# rgb_led_watch_2.net
KiCad netlist of a schematic drawn in EAGLE
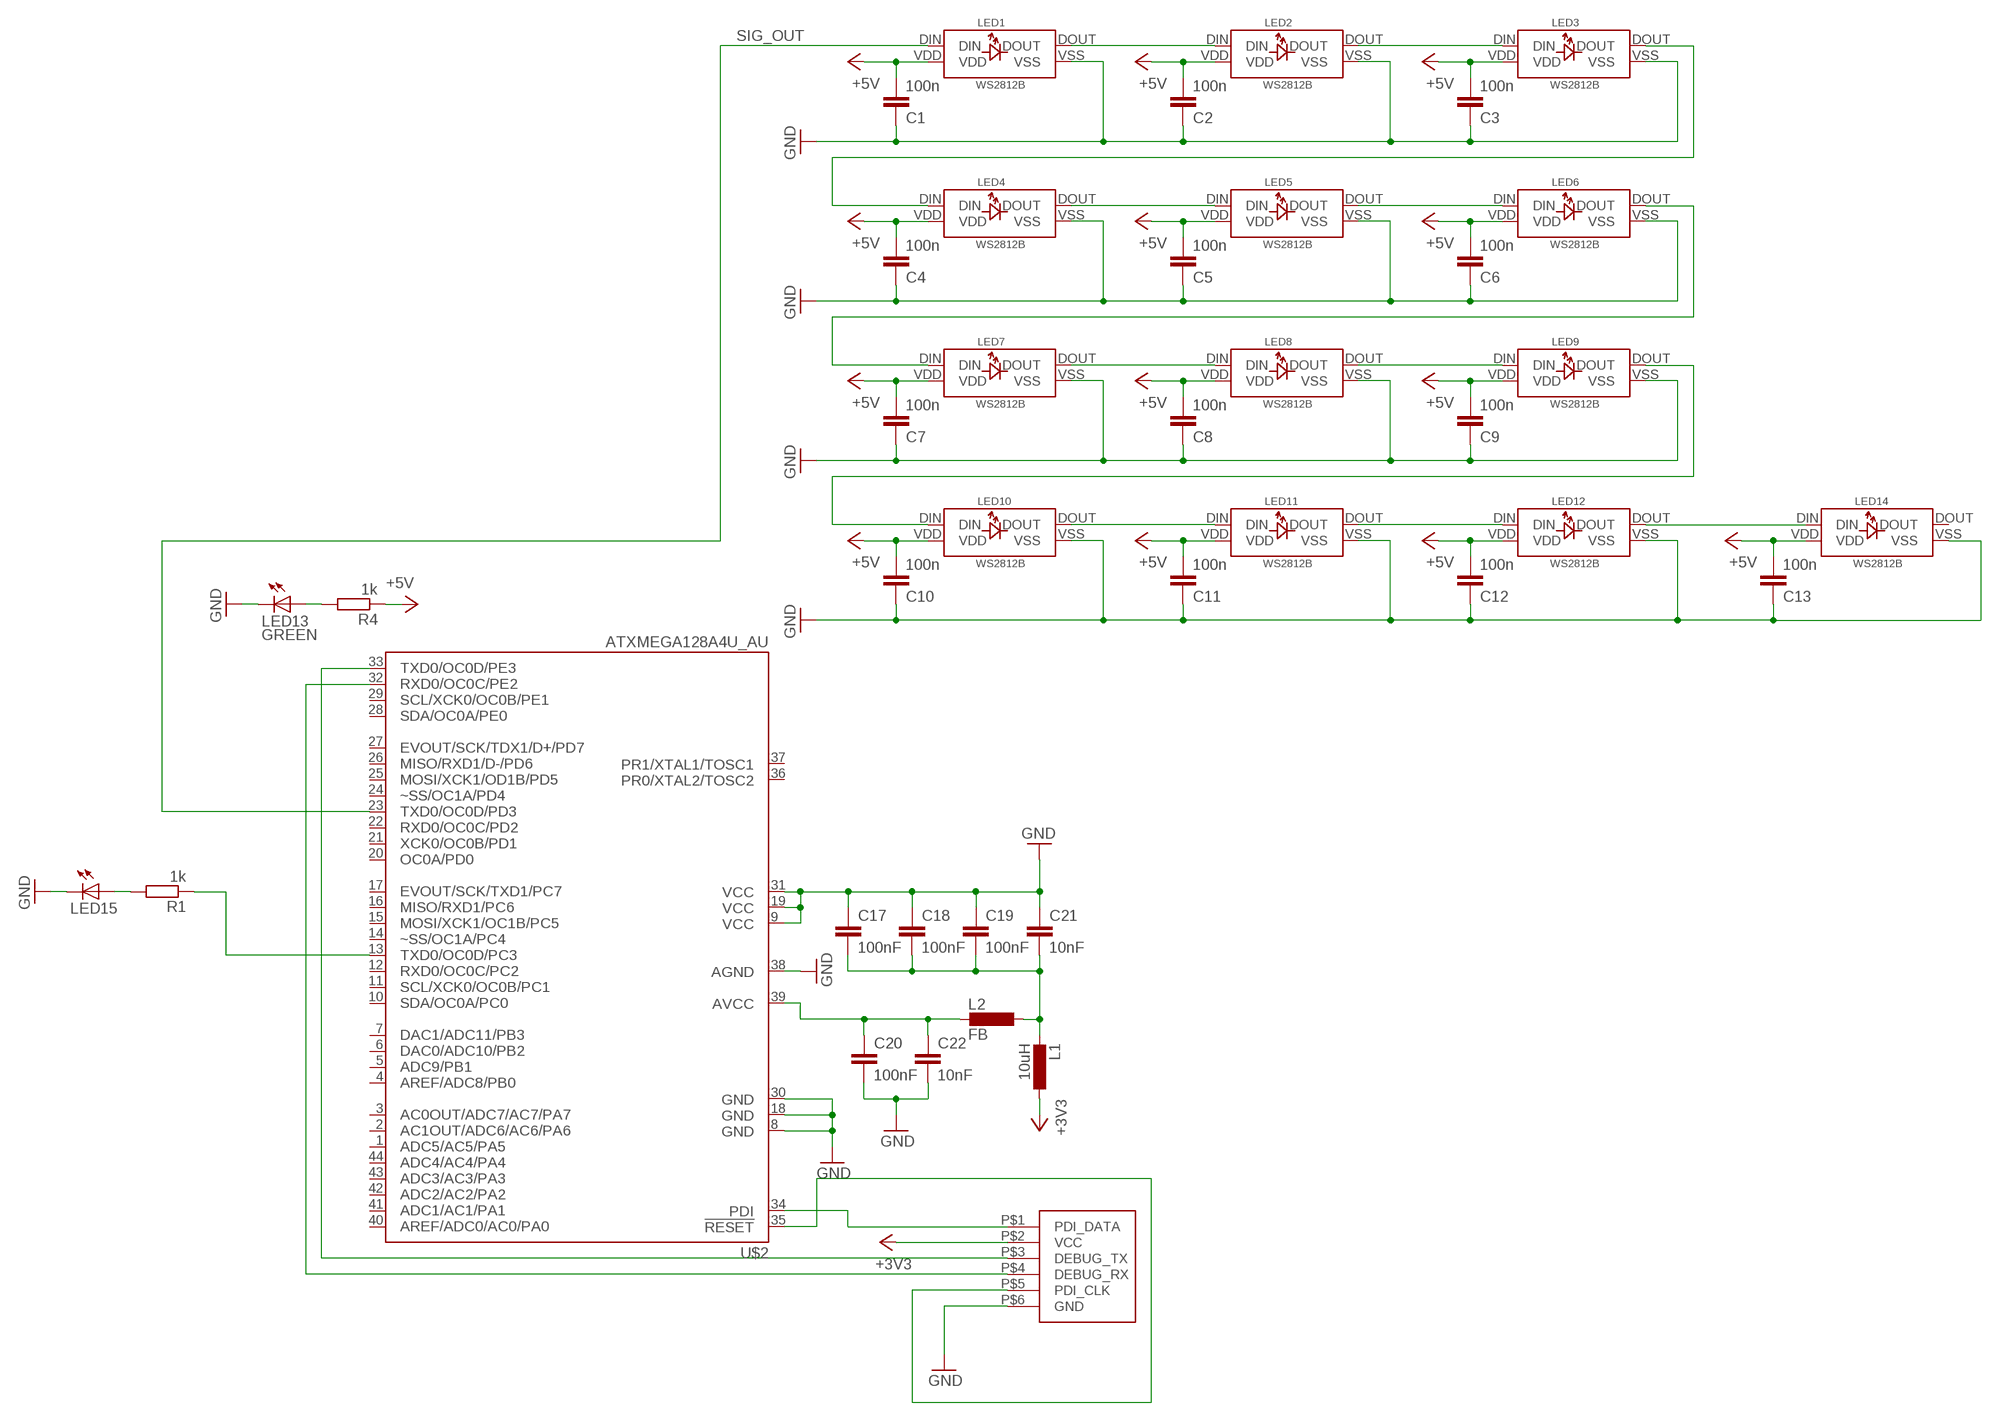
[diagram p0: schematic, sheet 1]

(export (version "E")
  (design (tool "Eeschema 10.0.6"))
  (components
    (comp (ref "C1")
      (value "100n")
      (footprint "eagle-import:C0603")
      (libsource (lib "eagle-import") (part "resistor_C-EUC0603"))
    )
    (comp (ref "C2")
      (value "100n")
      (footprint "eagle-import:C0603")
      (libsource (lib "eagle-import") (part "resistor_C-EUC0603"))
    )
    (comp (ref "C3")
      (value "100n")
      (footprint "eagle-import:C0603")
      (libsource (lib "eagle-import") (part "resistor_C-EUC0603"))
    )
    (comp (ref "C4")
      (value "100n")
      (footprint "eagle-import:C0603")
      (libsource (lib "eagle-import") (part "resistor_C-EUC0603"))
    )
    (comp (ref "C5")
      (value "100n")
      (footprint "eagle-import:C0603")
      (libsource (lib "eagle-import") (part "resistor_C-EUC0603"))
    )
    (comp (ref "C6")
      (value "100n")
      (footprint "eagle-import:C0603")
      (libsource (lib "eagle-import") (part "resistor_C-EUC0603"))
    )
    (comp (ref "C7")
      (value "100n")
      (footprint "eagle-import:C0603")
      (libsource (lib "eagle-import") (part "resistor_C-EUC0603"))
    )
    (comp (ref "C8")
      (value "100n")
      (footprint "eagle-import:C0603")
      (libsource (lib "eagle-import") (part "resistor_C-EUC0603"))
    )
    (comp (ref "C9")
      (value "100n")
      (footprint "eagle-import:C0603")
      (libsource (lib "eagle-import") (part "resistor_C-EUC0603"))
    )
    (comp (ref "C10")
      (value "100n")
      (footprint "eagle-import:C0603")
      (libsource (lib "eagle-import") (part "resistor_C-EUC0603"))
    )
    (comp (ref "C11")
      (value "100n")
      (footprint "eagle-import:C0603")
      (libsource (lib "eagle-import") (part "resistor_C-EUC0603"))
    )
    (comp (ref "C12")
      (value "100n")
      (footprint "eagle-import:C0603")
      (libsource (lib "eagle-import") (part "resistor_C-EUC0603"))
    )
    (comp (ref "C13")
      (value "100n")
      (footprint "eagle-import:C0603")
      (libsource (lib "eagle-import") (part "resistor_C-EUC0603"))
    )
    (comp (ref "C17")
      (value "100nF")
      (footprint "eagle-import:C0306")
      (libsource (lib "eagle-import") (part "C-EUC0306"))
    )
    (comp (ref "C18")
      (value "100nF")
      (footprint "eagle-import:C0306")
      (libsource (lib "eagle-import") (part "C-EUC0306"))
    )
    (comp (ref "C19")
      (value "100nF")
      (footprint "eagle-import:C0306")
      (libsource (lib "eagle-import") (part "C-EUC0306"))
    )
    (comp (ref "C20")
      (value "100nF")
      (footprint "eagle-import:C0306")
      (libsource (lib "eagle-import") (part "C-EUC0306"))
    )
    (comp (ref "C21")
      (value "10nF")
      (footprint "eagle-import:C0805")
      (libsource (lib "eagle-import") (part "C-EUC0805"))
    )
    (comp (ref "C22")
      (value "10nF")
      (footprint "eagle-import:C0805")
      (libsource (lib "eagle-import") (part "C-EUC0805"))
    )
    (comp (ref "L1")
      (value "10uH")
      (footprint "eagle-import:R0805")
      (libsource (lib "eagle-import") (part "L-EUSMD0805"))
    )
    (comp (ref "L2")
      (value "FB")
      (footprint "eagle-import:R0603")
      (libsource (lib "eagle-import") (part "L-EUSMD0603"))
    )
    (comp (ref "LED1")
      (value "WS2812B")
      (footprint "eagle-import:WS2812B")
      (libsource (lib "eagle-import") (part "WS2812B"))
    )
    (comp (ref "LED2")
      (value "WS2812B")
      (footprint "eagle-import:WS2812B")
      (libsource (lib "eagle-import") (part "WS2812B"))
    )
    (comp (ref "LED3")
      (value "WS2812B")
      (footprint "eagle-import:WS2812B")
      (libsource (lib "eagle-import") (part "WS2812B"))
    )
    (comp (ref "LED4")
      (value "WS2812B")
      (footprint "eagle-import:WS2812B")
      (libsource (lib "eagle-import") (part "WS2812B"))
    )
    (comp (ref "LED5")
      (value "WS2812B")
      (footprint "eagle-import:WS2812B")
      (libsource (lib "eagle-import") (part "WS2812B"))
    )
    (comp (ref "LED6")
      (value "WS2812B")
      (footprint "eagle-import:WS2812B")
      (libsource (lib "eagle-import") (part "WS2812B"))
    )
    (comp (ref "LED7")
      (value "WS2812B")
      (footprint "eagle-import:WS2812B")
      (libsource (lib "eagle-import") (part "WS2812B"))
    )
    (comp (ref "LED8")
      (value "WS2812B")
      (footprint "eagle-import:WS2812B")
      (libsource (lib "eagle-import") (part "WS2812B"))
    )
    (comp (ref "LED9")
      (value "WS2812B")
      (footprint "eagle-import:WS2812B")
      (libsource (lib "eagle-import") (part "WS2812B"))
    )
    (comp (ref "LED10")
      (value "WS2812B")
      (footprint "eagle-import:WS2812B")
      (libsource (lib "eagle-import") (part "WS2812B"))
    )
    (comp (ref "LED11")
      (value "WS2812B")
      (footprint "eagle-import:WS2812B")
      (libsource (lib "eagle-import") (part "WS2812B"))
    )
    (comp (ref "LED12")
      (value "WS2812B")
      (footprint "eagle-import:WS2812B")
      (libsource (lib "eagle-import") (part "WS2812B"))
    )
    (comp (ref "LED13")
      (value "GREEN")
      (footprint "eagle-import:CHIPLED_0603")
      (libsource (lib "eagle-import") (part "LEDCHIPLED_0603"))
    )
    (comp (ref "LED14")
      (value "WS2812B")
      (footprint "eagle-import:WS2812B")
      (libsource (lib "eagle-import") (part "WS2812B"))
    )
    (comp (ref "LED15")
      (value "LED5MM")
      (footprint "eagle-import:LED5MM")
      (libsource (lib "eagle-import") (part "LED5MM"))
    )
    (comp (ref "R1")
      (value "1k")
      (footprint "eagle-import:R0603")
      (libsource (lib "eagle-import") (part "R-EU_R0603"))
    )
    (comp (ref "R4")
      (value "1k")
      (footprint "eagle-import:R0603")
      (libsource (lib "eagle-import") (part "R-EU_R0603"))
    )
    (comp (ref "U$1")
      (value "CON_PROG-6CORN")
      (footprint "eagle-import:SMD-6-CORNER")
      (libsource (lib "eagle-import") (part "CON_PROG-6CORN"))
    )
    (comp (ref "U$2")
      (value "ATXMEGA128A4U_AU")
      (footprint "eagle-import:TQFP44")
      (libsource (lib "eagle-import") (part "ATXMEGAA4U_AU128"))
    )
  )
  (nets
    (net (code "1") (name "+3V3") (class "Default")
      (node (ref "L1") (pin "1") (pinfunction "1_1") (pintype "passive"))
      (node (ref "U$1") (pin "P$2") (pinfunction "VCC_P$2") (pintype "bidirectional"))
    )
    (net (code "2") (name "+5V") (class "Default")
      (node (ref "C1") (pin "2") (pinfunction "2_2") (pintype "passive"))
      (node (ref "C10") (pin "2") (pinfunction "2_2") (pintype "passive"))
      (node (ref "C11") (pin "2") (pinfunction "2_2") (pintype "passive"))
      (node (ref "C12") (pin "2") (pinfunction "2_2") (pintype "passive"))
      (node (ref "C13") (pin "2") (pinfunction "2_2") (pintype "passive"))
      (node (ref "C2") (pin "2") (pinfunction "2_2") (pintype "passive"))
      (node (ref "C3") (pin "2") (pinfunction "2_2") (pintype "passive"))
      (node (ref "C4") (pin "2") (pinfunction "2_2") (pintype "passive"))
      (node (ref "C5") (pin "2") (pinfunction "2_2") (pintype "passive"))
      (node (ref "C6") (pin "2") (pinfunction "2_2") (pintype "passive"))
      (node (ref "C7") (pin "2") (pinfunction "2_2") (pintype "passive"))
      (node (ref "C8") (pin "2") (pinfunction "2_2") (pintype "passive"))
      (node (ref "C9") (pin "2") (pinfunction "2_2") (pintype "passive"))
      (node (ref "LED1") (pin "VDD") (pinfunction "VDD_VDD") (pintype "power_in"))
      (node (ref "LED10") (pin "VDD") (pinfunction "VDD_VDD") (pintype "power_in"))
      (node (ref "LED11") (pin "VDD") (pinfunction "VDD_VDD") (pintype "power_in"))
      (node (ref "LED12") (pin "VDD") (pinfunction "VDD_VDD") (pintype "power_in"))
      (node (ref "LED14") (pin "VDD") (pinfunction "VDD_VDD") (pintype "power_in"))
      (node (ref "LED2") (pin "VDD") (pinfunction "VDD_VDD") (pintype "power_in"))
      (node (ref "LED3") (pin "VDD") (pinfunction "VDD_VDD") (pintype "power_in"))
      (node (ref "LED4") (pin "VDD") (pinfunction "VDD_VDD") (pintype "power_in"))
      (node (ref "LED5") (pin "VDD") (pinfunction "VDD_VDD") (pintype "power_in"))
      (node (ref "LED6") (pin "VDD") (pinfunction "VDD_VDD") (pintype "power_in"))
      (node (ref "LED7") (pin "VDD") (pinfunction "VDD_VDD") (pintype "power_in"))
      (node (ref "LED8") (pin "VDD") (pinfunction "VDD_VDD") (pintype "power_in"))
      (node (ref "LED9") (pin "VDD") (pinfunction "VDD_VDD") (pintype "power_in"))
      (node (ref "R4") (pin "1") (pinfunction "1_1") (pintype "passive"))
    )
    (net (code "3") (name "/SIG_OUT") (class "Default")
      (node (ref "LED1") (pin "DIN") (pinfunction "DIN_DIN") (pintype "input"))
      (node (ref "U$2") (pin "23") (pinfunction "PD3_23") (pintype "bidirectional"))
    )
    (net (code "4") (name "GND") (class "Default")
      (node (ref "C1") (pin "1") (pinfunction "1_1") (pintype "passive"))
      (node (ref "C10") (pin "1") (pinfunction "1_1") (pintype "passive"))
      (node (ref "C11") (pin "1") (pinfunction "1_1") (pintype "passive"))
      (node (ref "C12") (pin "1") (pinfunction "1_1") (pintype "passive"))
      (node (ref "C13") (pin "1") (pinfunction "1_1") (pintype "passive"))
      (node (ref "C17") (pin "1") (pinfunction "1_1") (pintype "passive"))
      (node (ref "C18") (pin "1") (pinfunction "1_1") (pintype "passive"))
      (node (ref "C19") (pin "1") (pinfunction "1_1") (pintype "passive"))
      (node (ref "C2") (pin "1") (pinfunction "1_1") (pintype "passive"))
      (node (ref "C20") (pin "2") (pinfunction "2_2") (pintype "passive"))
      (node (ref "C21") (pin "1") (pinfunction "1_1") (pintype "passive"))
      (node (ref "C22") (pin "2") (pinfunction "2_2") (pintype "passive"))
      (node (ref "C3") (pin "1") (pinfunction "1_1") (pintype "passive"))
      (node (ref "C4") (pin "1") (pinfunction "1_1") (pintype "passive"))
      (node (ref "C5") (pin "1") (pinfunction "1_1") (pintype "passive"))
      (node (ref "C6") (pin "1") (pinfunction "1_1") (pintype "passive"))
      (node (ref "C7") (pin "1") (pinfunction "1_1") (pintype "passive"))
      (node (ref "C8") (pin "1") (pinfunction "1_1") (pintype "passive"))
      (node (ref "C9") (pin "1") (pinfunction "1_1") (pintype "passive"))
      (node (ref "LED1") (pin "VSS") (pinfunction "VSS_VSS") (pintype "power_in"))
      (node (ref "LED10") (pin "VSS") (pinfunction "VSS_VSS") (pintype "power_in"))
      (node (ref "LED11") (pin "VSS") (pinfunction "VSS_VSS") (pintype "power_in"))
      (node (ref "LED12") (pin "VSS") (pinfunction "VSS_VSS") (pintype "power_in"))
      (node (ref "LED13") (pin "C") (pinfunction "C_C") (pintype "passive"))
      (node (ref "LED14") (pin "VSS") (pinfunction "VSS_VSS") (pintype "power_in"))
      (node (ref "LED15") (pin "K") (pinfunction "C_K") (pintype "passive"))
      (node (ref "LED2") (pin "VSS") (pinfunction "VSS_VSS") (pintype "power_in"))
      (node (ref "LED3") (pin "VSS") (pinfunction "VSS_VSS") (pintype "power_in"))
      (node (ref "LED4") (pin "VSS") (pinfunction "VSS_VSS") (pintype "power_in"))
      (node (ref "LED5") (pin "VSS") (pinfunction "VSS_VSS") (pintype "power_in"))
      (node (ref "LED6") (pin "VSS") (pinfunction "VSS_VSS") (pintype "power_in"))
      (node (ref "LED7") (pin "VSS") (pinfunction "VSS_VSS") (pintype "power_in"))
      (node (ref "LED8") (pin "VSS") (pinfunction "VSS_VSS") (pintype "power_in"))
      (node (ref "LED9") (pin "VSS") (pinfunction "VSS_VSS") (pintype "power_in"))
      (node (ref "U$1") (pin "P$6") (pinfunction "GND_P$6") (pintype "bidirectional"))
      (node (ref "U$2") (pin "18") (pinfunction "GND2_18") (pintype "bidirectional"))
      (node (ref "U$2") (pin "19") (pinfunction "VCC2_19") (pintype "bidirectional"))
      (node (ref "U$2") (pin "30") (pinfunction "GND3_30") (pintype "bidirectional"))
      (node (ref "U$2") (pin "31") (pinfunction "VCC3_31") (pintype "bidirectional"))
      (node (ref "U$2") (pin "38") (pinfunction "AGND_38") (pintype "bidirectional"))
      (node (ref "U$2") (pin "8") (pinfunction "GND1_8") (pintype "bidirectional"))
      (node (ref "U$2") (pin "9") (pinfunction "VCC1_9") (pintype "bidirectional"))
    )
    (net (code "5") (name "Net-(C17-Pad2)") (class "Default")
      (node (ref "C17") (pin "2") (pinfunction "2_2") (pintype "passive"))
      (node (ref "C18") (pin "2") (pinfunction "2_2") (pintype "passive"))
      (node (ref "C19") (pin "2") (pinfunction "2_2") (pintype "passive"))
      (node (ref "C21") (pin "2") (pinfunction "2_2") (pintype "passive"))
      (node (ref "L1") (pin "2") (pinfunction "2_2") (pintype "passive"))
      (node (ref "L2") (pin "1") (pinfunction "1_1") (pintype "passive"))
    )
    (net (code "6") (name "Net-(LED1-PadDOUT)") (class "Default")
      (node (ref "LED1") (pin "DOUT") (pinfunction "DOUT_DOUT") (pintype "output"))
      (node (ref "LED2") (pin "DIN") (pinfunction "DIN_DIN") (pintype "input"))
    )
    (net (code "7") (name "Net-(LED2-PadDOUT)") (class "Default")
      (node (ref "LED2") (pin "DOUT") (pinfunction "DOUT_DOUT") (pintype "output"))
      (node (ref "LED3") (pin "DIN") (pinfunction "DIN_DIN") (pintype "input"))
    )
    (net (code "8") (name "Net-(LED3-PadDOUT)") (class "Default")
      (node (ref "LED3") (pin "DOUT") (pinfunction "DOUT_DOUT") (pintype "output"))
      (node (ref "LED4") (pin "DIN") (pinfunction "DIN_DIN") (pintype "input"))
    )
    (net (code "9") (name "Net-(LED4-PadDOUT)") (class "Default")
      (node (ref "LED4") (pin "DOUT") (pinfunction "DOUT_DOUT") (pintype "output"))
      (node (ref "LED5") (pin "DIN") (pinfunction "DIN_DIN") (pintype "input"))
    )
    (net (code "10") (name "Net-(LED5-PadDOUT)") (class "Default")
      (node (ref "LED5") (pin "DOUT") (pinfunction "DOUT_DOUT") (pintype "output"))
      (node (ref "LED6") (pin "DIN") (pinfunction "DIN_DIN") (pintype "input"))
    )
    (net (code "11") (name "Net-(LED6-PadDOUT)") (class "Default")
      (node (ref "LED6") (pin "DOUT") (pinfunction "DOUT_DOUT") (pintype "output"))
      (node (ref "LED7") (pin "DIN") (pinfunction "DIN_DIN") (pintype "input"))
    )
    (net (code "12") (name "Net-(LED7-PadDOUT)") (class "Default")
      (node (ref "LED7") (pin "DOUT") (pinfunction "DOUT_DOUT") (pintype "output"))
      (node (ref "LED8") (pin "DIN") (pinfunction "DIN_DIN") (pintype "input"))
    )
    (net (code "13") (name "Net-(LED8-PadDOUT)") (class "Default")
      (node (ref "LED8") (pin "DOUT") (pinfunction "DOUT_DOUT") (pintype "output"))
      (node (ref "LED9") (pin "DIN") (pinfunction "DIN_DIN") (pintype "input"))
    )
    (net (code "14") (name "Net-(LED10-PadDIN)") (class "Default")
      (node (ref "LED10") (pin "DIN") (pinfunction "DIN_DIN") (pintype "input"))
      (node (ref "LED9") (pin "DOUT") (pinfunction "DOUT_DOUT") (pintype "output"))
    )
    (net (code "15") (name "Net-(LED10-PadDOUT)") (class "Default")
      (node (ref "LED10") (pin "DOUT") (pinfunction "DOUT_DOUT") (pintype "output"))
      (node (ref "LED11") (pin "DIN") (pinfunction "DIN_DIN") (pintype "input"))
    )
    (net (code "16") (name "Net-(LED11-PadDOUT)") (class "Default")
      (node (ref "LED11") (pin "DOUT") (pinfunction "DOUT_DOUT") (pintype "output"))
      (node (ref "LED12") (pin "DIN") (pinfunction "DIN_DIN") (pintype "input"))
    )
    (net (code "17") (name "Net-(LED12-PadDOUT)") (class "Default")
      (node (ref "LED12") (pin "DOUT") (pinfunction "DOUT_DOUT") (pintype "output"))
      (node (ref "LED14") (pin "DIN") (pinfunction "DIN_DIN") (pintype "input"))
    )
    (net (code "18") (name "Net-(LED13-PadA)") (class "Default")
      (node (ref "LED13") (pin "A") (pinfunction "A_A") (pintype "passive"))
      (node (ref "R4") (pin "2") (pinfunction "2_2") (pintype "passive"))
    )
    (net (code "19") (name "Net-(LED15-PadA)") (class "Default")
      (node (ref "LED15") (pin "A") (pinfunction "A_A") (pintype "passive"))
      (node (ref "R1") (pin "2") (pinfunction "2_2") (pintype "passive"))
    )
    (net (code "20") (name "Net-(U$1-DEBUG_RX)") (class "Default")
      (node (ref "U$1") (pin "P$4") (pinfunction "DEBUG_RX_P$4") (pintype "bidirectional"))
      (node (ref "U$2") (pin "32") (pinfunction "PE2_32") (pintype "bidirectional"))
    )
    (net (code "21") (name "Net-(U$1-DEBUG_TX)") (class "Default")
      (node (ref "U$1") (pin "P$3") (pinfunction "DEBUG_TX_P$3") (pintype "bidirectional"))
      (node (ref "U$2") (pin "33") (pinfunction "PE3_33") (pintype "bidirectional"))
    )
    (net (code "22") (name "Net-(U$1-PDI_CLK)") (class "Default")
      (node (ref "U$1") (pin "P$5") (pinfunction "PDI_CLK_P$5") (pintype "bidirectional"))
      (node (ref "U$2") (pin "35") (pinfunction "RESET_35") (pintype "bidirectional"))
    )
    (net (code "23") (name "Net-(U$1-PDI_DATA)") (class "Default")
      (node (ref "U$1") (pin "P$1") (pinfunction "PDI_DATA_P$1") (pintype "bidirectional"))
      (node (ref "U$2") (pin "34") (pinfunction "PDI_DATA_34") (pintype "bidirectional"))
    )
    (net (code "24") (name "Net-(U$2-AVCC)") (class "Default")
      (node (ref "C20") (pin "1") (pinfunction "1_1") (pintype "passive"))
      (node (ref "C22") (pin "1") (pinfunction "1_1") (pintype "passive"))
      (node (ref "L2") (pin "2") (pinfunction "2_2") (pintype "passive"))
      (node (ref "U$2") (pin "39") (pinfunction "AVCC_39") (pintype "bidirectional"))
    )
    (net (code "25") (name "Net-(U$2-PC3)") (class "Default")
      (node (ref "R1") (pin "1") (pinfunction "1_1") (pintype "passive"))
      (node (ref "U$2") (pin "13") (pinfunction "PC3_13") (pintype "bidirectional"))
    )
    (net (code "26") (name "unconnected-(LED14-PadDOUT)") (class "Default")
      (node (ref "LED14") (pin "DOUT") (pinfunction "DOUT_DOUT") (pintype "output"))
    )
    (net (code "27") (name "unconnected-(U$2-PA0-Pad40)") (class "Default")
      (node (ref "U$2") (pin "40") (pinfunction "PA0_40") (pintype "bidirectional"))
    )
    (net (code "28") (name "unconnected-(U$2-PA1-Pad41)") (class "Default")
      (node (ref "U$2") (pin "41") (pinfunction "PA1_41") (pintype "bidirectional"))
    )
    (net (code "29") (name "unconnected-(U$2-PA2-Pad42)") (class "Default")
      (node (ref "U$2") (pin "42") (pinfunction "PA2_42") (pintype "bidirectional"))
    )
    (net (code "30") (name "unconnected-(U$2-PA3-Pad43)") (class "Default")
      (node (ref "U$2") (pin "43") (pinfunction "PA3_43") (pintype "bidirectional"))
    )
    (net (code "31") (name "unconnected-(U$2-PA4-Pad44)") (class "Default")
      (node (ref "U$2") (pin "44") (pinfunction "PA4_44") (pintype "bidirectional"))
    )
    (net (code "32") (name "unconnected-(U$2-PA5-Pad1)") (class "Default")
      (node (ref "U$2") (pin "1") (pinfunction "PA5_1") (pintype "bidirectional"))
    )
    (net (code "33") (name "unconnected-(U$2-PA6-Pad2)") (class "Default")
      (node (ref "U$2") (pin "2") (pinfunction "PA6_2") (pintype "bidirectional"))
    )
    (net (code "34") (name "unconnected-(U$2-PA7-Pad3)") (class "Default")
      (node (ref "U$2") (pin "3") (pinfunction "PA7_3") (pintype "bidirectional"))
    )
    (net (code "35") (name "unconnected-(U$2-PB0-Pad4)") (class "Default")
      (node (ref "U$2") (pin "4") (pinfunction "PB0_4") (pintype "bidirectional"))
    )
    (net (code "36") (name "unconnected-(U$2-PB1-Pad5)") (class "Default")
      (node (ref "U$2") (pin "5") (pinfunction "PB1_5") (pintype "bidirectional"))
    )
    (net (code "37") (name "unconnected-(U$2-PB2-Pad6)") (class "Default")
      (node (ref "U$2") (pin "6") (pinfunction "PB2_6") (pintype "bidirectional"))
    )
    (net (code "38") (name "unconnected-(U$2-PB3-Pad7)") (class "Default")
      (node (ref "U$2") (pin "7") (pinfunction "PB3_7") (pintype "bidirectional"))
    )
    (net (code "39") (name "unconnected-(U$2-PC0-Pad10)") (class "Default")
      (node (ref "U$2") (pin "10") (pinfunction "PC0_10") (pintype "bidirectional"))
    )
    (net (code "40") (name "unconnected-(U$2-PC1-Pad11)") (class "Default")
      (node (ref "U$2") (pin "11") (pinfunction "PC1_11") (pintype "bidirectional"))
    )
    (net (code "41") (name "unconnected-(U$2-PC2-Pad12)") (class "Default")
      (node (ref "U$2") (pin "12") (pinfunction "PC2_12") (pintype "bidirectional"))
    )
    (net (code "42") (name "unconnected-(U$2-PC4-Pad14)") (class "Default")
      (node (ref "U$2") (pin "14") (pinfunction "PC4_14") (pintype "bidirectional"))
    )
    (net (code "43") (name "unconnected-(U$2-PC5-Pad15)") (class "Default")
      (node (ref "U$2") (pin "15") (pinfunction "PC5_15") (pintype "bidirectional"))
    )
    (net (code "44") (name "unconnected-(U$2-PC6-Pad16)") (class "Default")
      (node (ref "U$2") (pin "16") (pinfunction "PC6_16") (pintype "bidirectional"))
    )
    (net (code "45") (name "unconnected-(U$2-PC7-Pad17)") (class "Default")
      (node (ref "U$2") (pin "17") (pinfunction "PC7_17") (pintype "bidirectional"))
    )
    (net (code "46") (name "unconnected-(U$2-PD0-Pad20)") (class "Default")
      (node (ref "U$2") (pin "20") (pinfunction "PD0_20") (pintype "bidirectional"))
    )
    (net (code "47") (name "unconnected-(U$2-PD1-Pad21)") (class "Default")
      (node (ref "U$2") (pin "21") (pinfunction "PD1_21") (pintype "bidirectional"))
    )
    (net (code "48") (name "unconnected-(U$2-PD2-Pad22)") (class "Default")
      (node (ref "U$2") (pin "22") (pinfunction "PD2_22") (pintype "bidirectional"))
    )
    (net (code "49") (name "unconnected-(U$2-PD4-Pad24)") (class "Default")
      (node (ref "U$2") (pin "24") (pinfunction "PD4_24") (pintype "bidirectional"))
    )
    (net (code "50") (name "unconnected-(U$2-PD5-Pad25)") (class "Default")
      (node (ref "U$2") (pin "25") (pinfunction "PD5_25") (pintype "bidirectional"))
    )
    (net (code "51") (name "unconnected-(U$2-PD6-Pad26)") (class "Default")
      (node (ref "U$2") (pin "26") (pinfunction "PD6_26") (pintype "bidirectional"))
    )
    (net (code "52") (name "unconnected-(U$2-PD7-Pad27)") (class "Default")
      (node (ref "U$2") (pin "27") (pinfunction "PD7_27") (pintype "bidirectional"))
    )
    (net (code "53") (name "unconnected-(U$2-PE0-Pad28)") (class "Default")
      (node (ref "U$2") (pin "28") (pinfunction "PE0_28") (pintype "bidirectional"))
    )
    (net (code "54") (name "unconnected-(U$2-PE1-Pad29)") (class "Default")
      (node (ref "U$2") (pin "29") (pinfunction "PE1_29") (pintype "bidirectional"))
    )
    (net (code "55") (name "unconnected-(U$2-PR0-Pad36)") (class "Default")
      (node (ref "U$2") (pin "36") (pinfunction "PR0_36") (pintype "bidirectional"))
    )
    (net (code "56") (name "unconnected-(U$2-PR1-Pad37)") (class "Default")
      (node (ref "U$2") (pin "37") (pinfunction "PR1_37") (pintype "bidirectional"))
    )
  )
)
